# IE_ARSA_Merah_W_4_L.net
KiCad netlist of a schematic drawn in EAGLE
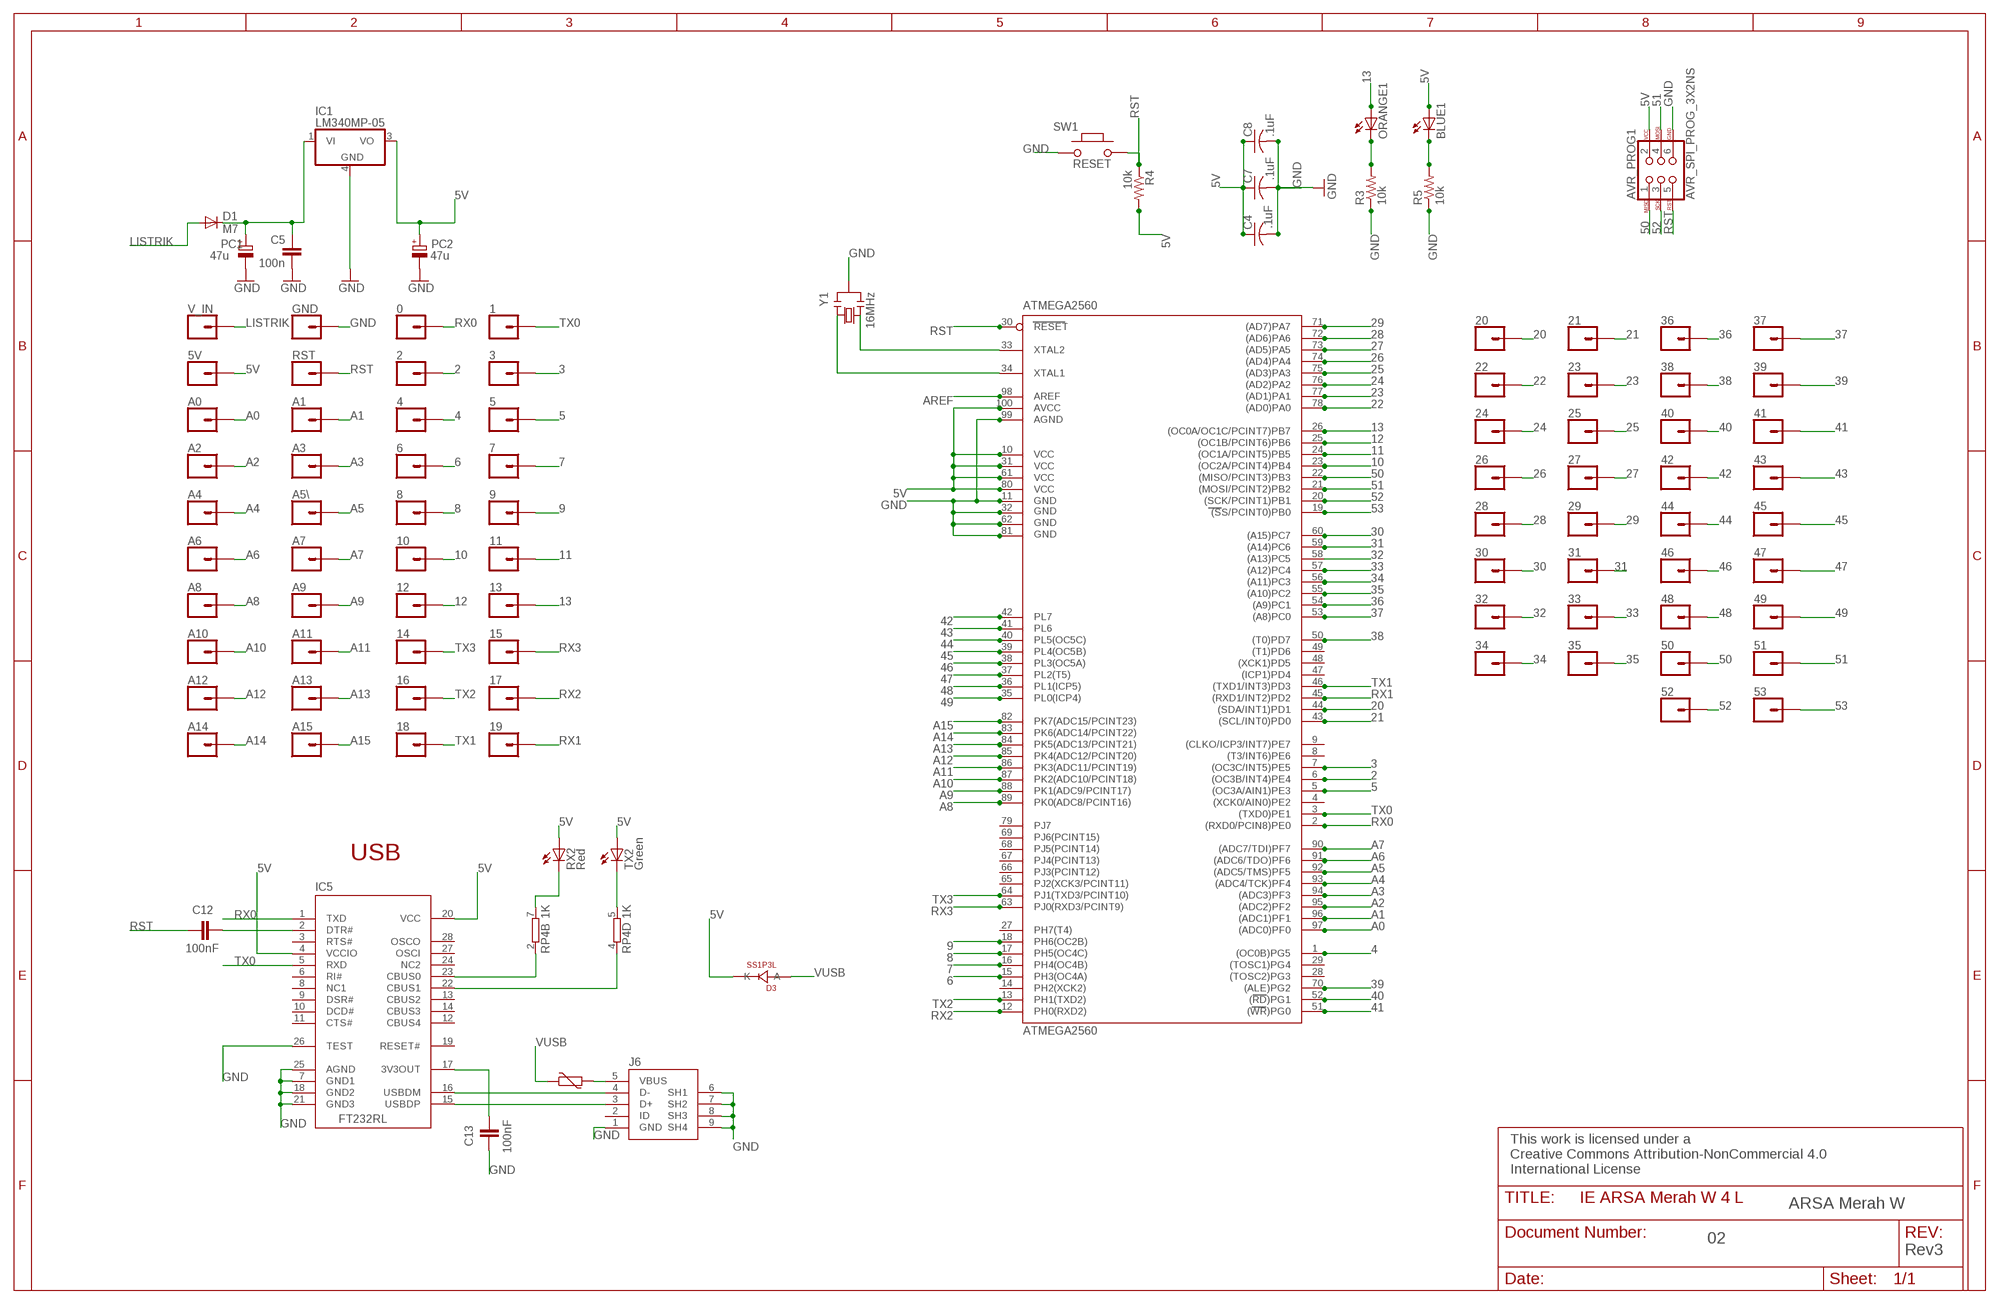
[diagram p0: schematic, sheet 1]

(export (version "E")
  (design (tool "Eeschema 10.0.6"))
  (components
    (comp (ref "0")
      (value "CONN_01")
      (footprint "eagle-import:1X01")
      (libsource (lib "eagle-import") (part "CONN_01"))
    )
    (comp (ref "1")
      (value "CONN_01")
      (footprint "eagle-import:1X01")
      (libsource (lib "eagle-import") (part "CONN_01"))
    )
    (comp (ref "2")
      (value "CONN_01")
      (footprint "eagle-import:1X01")
      (libsource (lib "eagle-import") (part "CONN_01"))
    )
    (comp (ref "3")
      (value "CONN_01")
      (footprint "eagle-import:1X01")
      (libsource (lib "eagle-import") (part "CONN_01"))
    )
    (comp (ref "4")
      (value "CONN_01")
      (footprint "eagle-import:1X01")
      (libsource (lib "eagle-import") (part "CONN_01"))
    )
    (comp (ref "5")
      (value "CONN_01")
      (footprint "eagle-import:1X01")
      (libsource (lib "eagle-import") (part "CONN_01"))
    )
    (comp (ref "5V")
      (value "CONN_01")
      (footprint "eagle-import:1X01")
      (libsource (lib "eagle-import") (part "CONN_01"))
    )
    (comp (ref "6")
      (value "CONN_01")
      (footprint "eagle-import:1X01")
      (libsource (lib "eagle-import") (part "CONN_01"))
    )
    (comp (ref "7")
      (value "CONN_01")
      (footprint "eagle-import:1X01")
      (libsource (lib "eagle-import") (part "CONN_01"))
    )
    (comp (ref "8")
      (value "CONN_01")
      (footprint "eagle-import:1X01")
      (libsource (lib "eagle-import") (part "CONN_01"))
    )
    (comp (ref "9")
      (value "CONN_01")
      (footprint "eagle-import:1X01")
      (libsource (lib "eagle-import") (part "CONN_01"))
    )
    (comp (ref "10")
      (value "CONN_01")
      (footprint "eagle-import:1X01")
      (libsource (lib "eagle-import") (part "CONN_01"))
    )
    (comp (ref "11")
      (value "CONN_01")
      (footprint "eagle-import:1X01")
      (libsource (lib "eagle-import") (part "CONN_01"))
    )
    (comp (ref "12")
      (value "CONN_01")
      (footprint "eagle-import:1X01")
      (libsource (lib "eagle-import") (part "CONN_01"))
    )
    (comp (ref "13")
      (value "CONN_01")
      (footprint "eagle-import:1X01")
      (libsource (lib "eagle-import") (part "CONN_01"))
    )
    (comp (ref "14")
      (value "CONN_01")
      (footprint "eagle-import:1X01")
      (libsource (lib "eagle-import") (part "CONN_01"))
    )
    (comp (ref "15")
      (value "CONN_01")
      (footprint "eagle-import:1X01")
      (libsource (lib "eagle-import") (part "CONN_01"))
    )
    (comp (ref "16")
      (value "CONN_01")
      (footprint "eagle-import:1X01")
      (libsource (lib "eagle-import") (part "CONN_01"))
    )
    (comp (ref "17")
      (value "CONN_01")
      (footprint "eagle-import:1X01")
      (libsource (lib "eagle-import") (part "CONN_01"))
    )
    (comp (ref "18")
      (value "CONN_01")
      (footprint "eagle-import:1X01")
      (libsource (lib "eagle-import") (part "CONN_01"))
    )
    (comp (ref "19")
      (value "CONN_01")
      (footprint "eagle-import:1X01")
      (libsource (lib "eagle-import") (part "CONN_01"))
    )
    (comp (ref "20")
      (value "CONN_01")
      (footprint "eagle-import:1X01")
      (libsource (lib "eagle-import") (part "CONN_01"))
    )
    (comp (ref "21")
      (value "CONN_01")
      (footprint "eagle-import:1X01")
      (libsource (lib "eagle-import") (part "CONN_01"))
    )
    (comp (ref "22")
      (value "CONN_01")
      (footprint "eagle-import:1X01")
      (libsource (lib "eagle-import") (part "CONN_01"))
    )
    (comp (ref "23")
      (value "CONN_01")
      (footprint "eagle-import:1X01")
      (libsource (lib "eagle-import") (part "CONN_01"))
    )
    (comp (ref "24")
      (value "CONN_01")
      (footprint "eagle-import:1X01")
      (libsource (lib "eagle-import") (part "CONN_01"))
    )
    (comp (ref "25")
      (value "CONN_01")
      (footprint "eagle-import:1X01")
      (libsource (lib "eagle-import") (part "CONN_01"))
    )
    (comp (ref "26")
      (value "CONN_01")
      (footprint "eagle-import:1X01")
      (libsource (lib "eagle-import") (part "CONN_01"))
    )
    (comp (ref "27")
      (value "CONN_01")
      (footprint "eagle-import:1X01")
      (libsource (lib "eagle-import") (part "CONN_01"))
    )
    (comp (ref "28")
      (value "CONN_01")
      (footprint "eagle-import:1X01")
      (libsource (lib "eagle-import") (part "CONN_01"))
    )
    (comp (ref "29")
      (value "CONN_01")
      (footprint "eagle-import:1X01")
      (libsource (lib "eagle-import") (part "CONN_01"))
    )
    (comp (ref "30")
      (value "CONN_01")
      (footprint "eagle-import:1X01")
      (libsource (lib "eagle-import") (part "CONN_01"))
    )
    (comp (ref "31")
      (value "CONN_01")
      (footprint "eagle-import:1X01")
      (libsource (lib "eagle-import") (part "CONN_01"))
    )
    (comp (ref "32")
      (value "CONN_01")
      (footprint "eagle-import:1X01")
      (libsource (lib "eagle-import") (part "CONN_01"))
    )
    (comp (ref "33")
      (value "CONN_01")
      (footprint "eagle-import:1X01")
      (libsource (lib "eagle-import") (part "CONN_01"))
    )
    (comp (ref "34")
      (value "CONN_01")
      (footprint "eagle-import:1X01")
      (libsource (lib "eagle-import") (part "CONN_01"))
    )
    (comp (ref "35")
      (value "CONN_01")
      (footprint "eagle-import:1X01")
      (libsource (lib "eagle-import") (part "CONN_01"))
    )
    (comp (ref "36")
      (value "CONN_01")
      (footprint "eagle-import:1X01")
      (libsource (lib "eagle-import") (part "CONN_01"))
    )
    (comp (ref "37")
      (value "CONN_01")
      (footprint "eagle-import:1X01")
      (libsource (lib "eagle-import") (part "CONN_01"))
    )
    (comp (ref "38")
      (value "CONN_01")
      (footprint "eagle-import:1X01")
      (libsource (lib "eagle-import") (part "CONN_01"))
    )
    (comp (ref "39")
      (value "CONN_01")
      (footprint "eagle-import:1X01")
      (libsource (lib "eagle-import") (part "CONN_01"))
    )
    (comp (ref "40")
      (value "CONN_01")
      (footprint "eagle-import:1X01")
      (libsource (lib "eagle-import") (part "CONN_01"))
    )
    (comp (ref "41")
      (value "CONN_01")
      (footprint "eagle-import:1X01")
      (libsource (lib "eagle-import") (part "CONN_01"))
    )
    (comp (ref "42")
      (value "CONN_01")
      (footprint "eagle-import:1X01")
      (libsource (lib "eagle-import") (part "CONN_01"))
    )
    (comp (ref "43")
      (value "CONN_01")
      (footprint "eagle-import:1X01")
      (libsource (lib "eagle-import") (part "CONN_01"))
    )
    (comp (ref "44")
      (value "CONN_01")
      (footprint "eagle-import:1X01")
      (libsource (lib "eagle-import") (part "CONN_01"))
    )
    (comp (ref "45")
      (value "CONN_01")
      (footprint "eagle-import:1X01")
      (libsource (lib "eagle-import") (part "CONN_01"))
    )
    (comp (ref "46")
      (value "CONN_01")
      (footprint "eagle-import:1X01")
      (libsource (lib "eagle-import") (part "CONN_01"))
    )
    (comp (ref "47")
      (value "CONN_01")
      (footprint "eagle-import:1X01")
      (libsource (lib "eagle-import") (part "CONN_01"))
    )
    (comp (ref "48")
      (value "CONN_01")
      (footprint "eagle-import:1X01")
      (libsource (lib "eagle-import") (part "CONN_01"))
    )
    (comp (ref "49")
      (value "CONN_01")
      (footprint "eagle-import:1X01")
      (libsource (lib "eagle-import") (part "CONN_01"))
    )
    (comp (ref "50")
      (value "CONN_01")
      (footprint "eagle-import:1X01")
      (libsource (lib "eagle-import") (part "CONN_01"))
    )
    (comp (ref "51")
      (value "CONN_01")
      (footprint "eagle-import:1X01")
      (libsource (lib "eagle-import") (part "CONN_01"))
    )
    (comp (ref "52")
      (value "CONN_01")
      (footprint "eagle-import:1X01")
      (libsource (lib "eagle-import") (part "CONN_01"))
    )
    (comp (ref "53")
      (value "CONN_01")
      (footprint "eagle-import:1X01")
      (libsource (lib "eagle-import") (part "CONN_01"))
    )
    (comp (ref "A0")
      (value "CONN_01")
      (footprint "eagle-import:1X01")
      (libsource (lib "eagle-import") (part "CONN_01"))
    )
    (comp (ref "A1")
      (value "CONN_01")
      (footprint "eagle-import:1X01")
      (libsource (lib "eagle-import") (part "CONN_01"))
    )
    (comp (ref "A2")
      (value "CONN_01")
      (footprint "eagle-import:1X01")
      (libsource (lib "eagle-import") (part "CONN_01"))
    )
    (comp (ref "A3")
      (value "CONN_01")
      (footprint "eagle-import:1X01")
      (libsource (lib "eagle-import") (part "CONN_01"))
    )
    (comp (ref "A4")
      (value "CONN_01")
      (footprint "eagle-import:1X01")
      (libsource (lib "eagle-import") (part "CONN_01"))
    )
    (comp (ref "A5\\")
      (value "CONN_01")
      (footprint "eagle-import:1X01")
      (libsource (lib "eagle-import") (part "CONN_01"))
    )
    (comp (ref "A6")
      (value "CONN_01")
      (footprint "eagle-import:1X01")
      (libsource (lib "eagle-import") (part "CONN_01"))
    )
    (comp (ref "A7")
      (value "CONN_01")
      (footprint "eagle-import:1X01")
      (libsource (lib "eagle-import") (part "CONN_01"))
    )
    (comp (ref "A8")
      (value "CONN_01")
      (footprint "eagle-import:1X01")
      (libsource (lib "eagle-import") (part "CONN_01"))
    )
    (comp (ref "A9")
      (value "CONN_01")
      (footprint "eagle-import:1X01")
      (libsource (lib "eagle-import") (part "CONN_01"))
    )
    (comp (ref "A10")
      (value "CONN_01")
      (footprint "eagle-import:1X01")
      (libsource (lib "eagle-import") (part "CONN_01"))
    )
    (comp (ref "A11")
      (value "CONN_01")
      (footprint "eagle-import:1X01")
      (libsource (lib "eagle-import") (part "CONN_01"))
    )
    (comp (ref "A12")
      (value "CONN_01")
      (footprint "eagle-import:1X01")
      (libsource (lib "eagle-import") (part "CONN_01"))
    )
    (comp (ref "A13")
      (value "CONN_01")
      (footprint "eagle-import:1X01")
      (libsource (lib "eagle-import") (part "CONN_01"))
    )
    (comp (ref "A14")
      (value "CONN_01")
      (footprint "eagle-import:1X01")
      (libsource (lib "eagle-import") (part "CONN_01"))
    )
    (comp (ref "A15")
      (value "CONN_01")
      (footprint "eagle-import:1X01")
      (libsource (lib "eagle-import") (part "CONN_01"))
    )
    (comp (ref "ATMEGA2560")
      (value "ATMEGA2560")
      (footprint "eagle-import:TQFP100")
      (libsource (lib "eagle-import") (part "ATMEGA2560"))
    )
    (comp (ref "AVR_PROG1")
      (value "AVR_SPI_PROG_3X2NS")
      (footprint "eagle-import:2X3-NS")
      (libsource (lib "eagle-import") (part "AVR_SPI_PROG_3X2NS"))
    )
    (comp (ref "BLUE1")
      (value "L")
      (footprint "eagle-import:SMD-0805-LED")
      (libsource (lib "eagle-import") (part "LED-SMD-0805"))
    )
    (comp (ref "C4")
      (value "CAPACITOR-SMD-0805")
      (footprint "eagle-import:SMD-0805")
      (libsource (lib "eagle-import") (part "CAPACITOR-SMD-0805"))
    )
    (comp (ref "C5")
      (value "100n")
      (footprint "eagle-import:C0603-ROUND")
      (libsource (lib "eagle-import") (part "C-EU0603-RND"))
    )
    (comp (ref "C7")
      (value ".1uF")
      (footprint "eagle-import:SMD-0805")
      (libsource (lib "eagle-import") (part "CAPACITOR-SMD-0805"))
    )
    (comp (ref "C8")
      (value ".1uF")
      (footprint "eagle-import:SMD-0805")
      (libsource (lib "eagle-import") (part "CAPACITOR-SMD-0805"))
    )
    (comp (ref "C12")
      (value "100nF")
      (footprint "eagle-import:C0603-ROUND")
      (fields (field (name "PART_NUMBER") "cl10b104kbnc"))
      (libsource (lib "eagle-import") (part "0015_100NF_0603"))
    )
    (comp (ref "C13")
      (value "100nF")
      (footprint "eagle-import:C0603-ROUND")
      (fields (field (name "PART_NUMBER") "cl10b104kbnc"))
      (libsource (lib "eagle-import") (part "0015_100NF_0603"))
    )
    (comp (ref "D1")
      (value "M7")
      (footprint "eagle-import:SMB")
      (libsource (lib "eagle-import") (part "DIODE-SMB"))
    )
    (comp (ref "D3")
      (value "SS1P3L")
      (footprint "eagle-import:DO220AAL")
      (fields (field (name "PART_NUMBER") "SS1P3L-M3/84A"))
      (libsource (lib "eagle-import") (part "0025_SS1P3L-M3/84A"))
    )
    (comp (ref "F3")
      (value "MFFSMF050")
      (footprint "eagle-import:0603-1608X90N")
      (fields (field (name "MANUFACTURER") "Bourns Inc "))
      (libsource (lib "eagle-import") (part "PTC"))
    )
    (comp (ref "GND")
      (value "CONN_01")
      (footprint "eagle-import:1X01")
      (libsource (lib "eagle-import") (part "CONN_01"))
    )
    (comp (ref "IC1")
      (value "LM340MP-05")
      (footprint "eagle-import:SOT223")
      (libsource (lib "eagle-import") (part "LM340?-MP05"))
    )
    (comp (ref "IC5")
      (value "FT232RL")
      (footprint "eagle-import:SSOP28")
      (libsource (lib "eagle-import") (part "0226_FT232RL"))
    )
    (comp (ref "J6")
      (value "0219_14850")
      (footprint "eagle-import:USB-MINI-B_2")
      (fields (field (name "PART_NUMBER") "14850"))
      (libsource (lib "eagle-import") (part "0219_14850"))
    )
    (comp (ref "ORANGE1")
      (value "L")
      (footprint "eagle-import:SMD-0805-LED")
      (libsource (lib "eagle-import") (part "LED-SMD-0805"))
    )
    (comp (ref "PC1")
      (value "47u")
      (footprint "eagle-import:PANASONIC_D")
      (libsource (lib "eagle-import") (part "CPOL-EUD"))
    )
    (comp (ref "PC2")
      (value "47u")
      (footprint "eagle-import:PANASONIC_D")
      (libsource (lib "eagle-import") (part "CPOL-EUD"))
    )
    (comp (ref "R3")
      (value "10k")
      (footprint "eagle-import:SMD-0805")
      (libsource (lib "eagle-import") (part "RESISTOR-SMD-0805"))
    )
    (comp (ref "R4")
      (value "10k")
      (footprint "eagle-import:SMD-0805")
      (libsource (lib "eagle-import") (part "RESISTOR-SMD-0805"))
    )
    (comp (ref "R5")
      (value "10k")
      (footprint "eagle-import:SMD-0805")
      (libsource (lib "eagle-import") (part "RESISTOR-SMD-0805"))
    )
    (comp (ref "RP4")
      (value "1K")
      (footprint "eagle-import:CAY16")
      (fields (field (name "PART_NUMBER") "064R_1K_/_CAY16-102J4LF"))
      (libsource (lib "eagle-import") (part "0005_064R_1K_/_CAY16-102J4LF"))
    )
    (comp (ref "RST")
      (value "CONN_01")
      (footprint "eagle-import:1X01")
      (libsource (lib "eagle-import") (part "CONN_01"))
    )
    (comp (ref "RX2")
      (value "Red")
      (footprint "eagle-import:CHIPLED_0805")
      (fields (field (name "PART_NUMBER") "KTP-2012SURCK"))
      (libsource (lib "eagle-import") (part "0181_KTP-2012SURCK"))
    )
    (comp (ref "SW1")
      (value "RESET")
      (footprint "eagle-import:SMD_157SW")
      (fields (field (name "PART_NUMBER") "IT-1185AP1C-160G-G_T&R"))
      (libsource (lib "eagle-import") (part "0173_IT-1185AP1C-160G-G_T&R"))
    )
    (comp (ref "TX2")
      (value "Green")
      (footprint "eagle-import:CHIPLED_0805")
      (fields (field (name "PART_NUMBER") "KPT-2012SGC"))
      (libsource (lib "eagle-import") (part "0043_KPT-2012SGC"))
    )
    (comp (ref "V_IN")
      (value "CONN_01")
      (footprint "eagle-import:1X01")
      (libsource (lib "eagle-import") (part "CONN_01"))
    )
    (comp (ref "Y1")
      (value "16MHz")
      (footprint "eagle-import:RESONATOR")
      (fields (field (name "PART_NUMBER") "CSTCE16M0V53-R0"))
      (libsource (lib "eagle-import") (part "0011_CSTCE16M0V53-R0"))
    )
  )
  (nets
    (net (code "1") (name "/LISTRIK") (class "Default")
      (node (ref "D1") (pin "A") (pinfunction "A_A") (pintype "passive"))
      (node (ref "V_IN") (pin "1") (pinfunction "1_1") (pintype "passive"))
    )
    (net (code "2") (name "/VUSB") (class "Default")
      (node (ref "D3") (pin "P$2") (pinfunction "A_P$2") (pintype "bidirectional"))
      (node (ref "F3") (pin "1") (pinfunction "1_1") (pintype "passive"))
    )
    (net (code "3") (name "2") (class "Default")
      (node (ref "2") (pin "1") (pinfunction "1_1") (pintype "passive"))
      (node (ref "ATMEGA2560") (pin "6") (pinfunction "(OC3B/INT4)PE4_6") (pintype "bidirectional"))
    )
    (net (code "4") (name "3") (class "Default")
      (node (ref "3") (pin "1") (pinfunction "1_1") (pintype "passive"))
      (node (ref "ATMEGA2560") (pin "7") (pinfunction "(OC3C/INT5)PE5_7") (pintype "bidirectional"))
    )
    (net (code "5") (name "4") (class "Default")
      (node (ref "4") (pin "1") (pinfunction "1_1") (pintype "passive"))
      (node (ref "ATMEGA2560") (pin "1") (pinfunction "(OC0B)PG5_1") (pintype "bidirectional"))
    )
    (net (code "6") (name "5") (class "Default")
      (node (ref "5") (pin "1") (pinfunction "1_1") (pintype "passive"))
      (node (ref "ATMEGA2560") (pin "5") (pinfunction "(OC3A/AIN1)PE3_5") (pintype "bidirectional"))
    )
    (net (code "7") (name "5V") (class "Default")
      (node (ref "5V") (pin "1") (pinfunction "1_1") (pintype "passive"))
      (node (ref "ATMEGA2560") (pin "10") (pinfunction "VCC_10") (pintype "power_in"))
      (node (ref "ATMEGA2560") (pin "100") (pinfunction "AVCC_100") (pintype "power_in"))
      (node (ref "ATMEGA2560") (pin "31") (pinfunction "VCC1_31") (pintype "power_in"))
      (node (ref "ATMEGA2560") (pin "61") (pinfunction "VCC2_61") (pintype "power_in"))
      (node (ref "ATMEGA2560") (pin "80") (pinfunction "VCC3_80") (pintype "power_in"))
      (node (ref "AVR_PROG1") (pin "2") (pinfunction "2_2") (pintype "passive"))
      (node (ref "BLUE1") (pin "1") (pinfunction "A_1") (pintype "passive"))
      (node (ref "C4") (pin "1") (pinfunction "1_1") (pintype "passive"))
      (node (ref "C7") (pin "1") (pinfunction "1_1") (pintype "passive"))
      (node (ref "C8") (pin "1") (pinfunction "1_1") (pintype "passive"))
      (node (ref "D3") (pin "P$1") (pinfunction "K_P$1") (pintype "bidirectional"))
      (node (ref "IC1") (pin "3") (pinfunction "VO_3") (pintype "passive"))
      (node (ref "IC5") (pin "20") (pinfunction "VCC_20") (pintype "power_in"))
      (node (ref "IC5") (pin "4") (pinfunction "VCCIO_4") (pintype "power_in"))
      (node (ref "PC2") (pin "+") (pinfunction "+_+") (pintype "passive"))
      (node (ref "R4") (pin "2") (pinfunction "2_2") (pintype "passive"))
      (node (ref "RX2") (pin "A") (pinfunction "A_A") (pintype "passive"))
      (node (ref "TX2") (pin "A") (pinfunction "A_A") (pintype "passive"))
    )
    (net (code "8") (name "6") (class "Default")
      (node (ref "6") (pin "1") (pinfunction "1_1") (pintype "passive"))
      (node (ref "ATMEGA2560") (pin "15") (pinfunction "PH3(OC4A)_15") (pintype "bidirectional"))
    )
    (net (code "9") (name "7") (class "Default")
      (node (ref "7") (pin "1") (pinfunction "1_1") (pintype "passive"))
      (node (ref "ATMEGA2560") (pin "16") (pinfunction "PH4(OC4B)_16") (pintype "bidirectional"))
    )
    (net (code "10") (name "8") (class "Default")
      (node (ref "8") (pin "1") (pinfunction "1_1") (pintype "passive"))
      (node (ref "ATMEGA2560") (pin "17") (pinfunction "PH5(OC4C)_17") (pintype "bidirectional"))
    )
    (net (code "11") (name "9") (class "Default")
      (node (ref "9") (pin "1") (pinfunction "1_1") (pintype "passive"))
      (node (ref "ATMEGA2560") (pin "18") (pinfunction "PH6(OC2B)_18") (pintype "bidirectional"))
    )
    (net (code "12") (name "10") (class "Default")
      (node (ref "10") (pin "1") (pinfunction "1_1") (pintype "passive"))
      (node (ref "ATMEGA2560") (pin "23") (pinfunction "(OC2A/PCINT4)PB4_23") (pintype "bidirectional"))
    )
    (net (code "13") (name "11") (class "Default")
      (node (ref "11") (pin "1") (pinfunction "1_1") (pintype "passive"))
      (node (ref "ATMEGA2560") (pin "24") (pinfunction "(OC1A/PCINT5)PB5_24") (pintype "bidirectional"))
    )
    (net (code "14") (name "12") (class "Default")
      (node (ref "12") (pin "1") (pinfunction "1_1") (pintype "passive"))
      (node (ref "ATMEGA2560") (pin "25") (pinfunction "(OC1B/PCINT6)PB6_25") (pintype "bidirectional"))
    )
    (net (code "15") (name "13") (class "Default")
      (node (ref "13") (pin "1") (pinfunction "1_1") (pintype "passive"))
      (node (ref "ATMEGA2560") (pin "26") (pinfunction "(OC0A/OC1C/PCINT7)PB7_26") (pintype "bidirectional"))
      (node (ref "ORANGE1") (pin "1") (pinfunction "A_1") (pintype "passive"))
    )
    (net (code "16") (name "20") (class "Default")
      (node (ref "20") (pin "1") (pinfunction "1_1") (pintype "passive"))
      (node (ref "ATMEGA2560") (pin "44") (pinfunction "(SDA/INT1)PD1_44") (pintype "bidirectional"))
    )
    (net (code "17") (name "21") (class "Default")
      (node (ref "21") (pin "1") (pinfunction "1_1") (pintype "passive"))
      (node (ref "ATMEGA2560") (pin "43") (pinfunction "(SCL/INT0)PD0_43") (pintype "bidirectional"))
    )
    (net (code "18") (name "22") (class "Default")
      (node (ref "22") (pin "1") (pinfunction "1_1") (pintype "passive"))
      (node (ref "ATMEGA2560") (pin "78") (pinfunction "(AD0)PA0_78") (pintype "bidirectional"))
    )
    (net (code "19") (name "23") (class "Default")
      (node (ref "23") (pin "1") (pinfunction "1_1") (pintype "passive"))
      (node (ref "ATMEGA2560") (pin "77") (pinfunction "(AD1)PA1_77") (pintype "bidirectional"))
    )
    (net (code "20") (name "24") (class "Default")
      (node (ref "24") (pin "1") (pinfunction "1_1") (pintype "passive"))
      (node (ref "ATMEGA2560") (pin "76") (pinfunction "(AD2)PA2_76") (pintype "bidirectional"))
    )
    (net (code "21") (name "25") (class "Default")
      (node (ref "25") (pin "1") (pinfunction "1_1") (pintype "passive"))
      (node (ref "ATMEGA2560") (pin "75") (pinfunction "(AD3)PA3_75") (pintype "bidirectional"))
    )
    (net (code "22") (name "26") (class "Default")
      (node (ref "26") (pin "1") (pinfunction "1_1") (pintype "passive"))
      (node (ref "ATMEGA2560") (pin "74") (pinfunction "(AD4)PA4_74") (pintype "bidirectional"))
    )
    (net (code "23") (name "27") (class "Default")
      (node (ref "27") (pin "1") (pinfunction "1_1") (pintype "passive"))
      (node (ref "ATMEGA2560") (pin "73") (pinfunction "(AD5)PA5_73") (pintype "bidirectional"))
    )
    (net (code "24") (name "28") (class "Default")
      (node (ref "28") (pin "1") (pinfunction "1_1") (pintype "passive"))
      (node (ref "ATMEGA2560") (pin "72") (pinfunction "(AD6)PA6_72") (pintype "bidirectional"))
    )
    (net (code "25") (name "29") (class "Default")
      (node (ref "29") (pin "1") (pinfunction "1_1") (pintype "passive"))
      (node (ref "ATMEGA2560") (pin "71") (pinfunction "(AD7)PA7_71") (pintype "bidirectional"))
    )
    (net (code "26") (name "30") (class "Default")
      (node (ref "30") (pin "1") (pinfunction "1_1") (pintype "passive"))
      (node (ref "ATMEGA2560") (pin "60") (pinfunction "(A15)PC7_60") (pintype "bidirectional"))
    )
    (net (code "27") (name "31") (class "Default")
      (node (ref "31") (pin "1") (pinfunction "1_1") (pintype "passive"))
      (node (ref "ATMEGA2560") (pin "59") (pinfunction "(A14)PC6_59") (pintype "bidirectional"))
    )
    (net (code "28") (name "32") (class "Default")
      (node (ref "32") (pin "1") (pinfunction "1_1") (pintype "passive"))
      (node (ref "ATMEGA2560") (pin "58") (pinfunction "(A13)PC5_58") (pintype "bidirectional"))
    )
    (net (code "29") (name "33") (class "Default")
      (node (ref "33") (pin "1") (pinfunction "1_1") (pintype "passive"))
      (node (ref "ATMEGA2560") (pin "57") (pinfunction "(A12)PC4_57") (pintype "bidirectional"))
    )
    (net (code "30") (name "34") (class "Default")
      (node (ref "34") (pin "1") (pinfunction "1_1") (pintype "passive"))
      (node (ref "ATMEGA2560") (pin "56") (pinfunction "(A11)PC3_56") (pintype "bidirectional"))
    )
    (net (code "31") (name "35") (class "Default")
      (node (ref "35") (pin "1") (pinfunction "1_1") (pintype "passive"))
      (node (ref "ATMEGA2560") (pin "55") (pinfunction "(A10)PC2_55") (pintype "bidirectional"))
    )
    (net (code "32") (name "36") (class "Default")
      (node (ref "36") (pin "1") (pinfunction "1_1") (pintype "passive"))
      (node (ref "ATMEGA2560") (pin "54") (pinfunction "(A9)PC1_54") (pintype "bidirectional"))
    )
    (net (code "33") (name "37") (class "Default")
      (node (ref "37") (pin "1") (pinfunction "1_1") (pintype "passive"))
      (node (ref "ATMEGA2560") (pin "53") (pinfunction "(A8)PC0_53") (pintype "bidirectional"))
    )
    (net (code "34") (name "38") (class "Default")
      (node (ref "38") (pin "1") (pinfunction "1_1") (pintype "passive"))
      (node (ref "ATMEGA2560") (pin "50") (pinfunction "(T0)PD7_50") (pintype "bidirectional"))
    )
    (net (code "35") (name "39") (class "Default")
      (node (ref "39") (pin "1") (pinfunction "1_1") (pintype "passive"))
      (node (ref "ATMEGA2560") (pin "70") (pinfunction "(ALE)PG2_70") (pintype "bidirectional"))
    )
    (net (code "36") (name "40") (class "Default")
      (node (ref "40") (pin "1") (pinfunction "1_1") (pintype "passive"))
      (node (ref "ATMEGA2560") (pin "52") (pinfunction "(RD)PG1_52") (pintype "bidirectional"))
    )
    (net (code "37") (name "41") (class "Default")
      (node (ref "41") (pin "1") (pinfunction "1_1") (pintype "passive"))
      (node (ref "ATMEGA2560") (pin "51") (pinfunction "(WR)PG0_51") (pintype "bidirectional"))
    )
    (net (code "38") (name "42") (class "Default")
      (node (ref "42") (pin "1") (pinfunction "1_1") (pintype "passive"))
      (node (ref "ATMEGA2560") (pin "42") (pinfunction "PL7_42") (pintype "bidirectional"))
    )
    (net (code "39") (name "43") (class "Default")
      (node (ref "43") (pin "1") (pinfunction "1_1") (pintype "passive"))
      (node (ref "ATMEGA2560") (pin "41") (pinfunction "PL6_41") (pintype "bidirectional"))
    )
    (net (code "40") (name "44") (class "Default")
      (node (ref "44") (pin "1") (pinfunction "1_1") (pintype "passive"))
      (node (ref "ATMEGA2560") (pin "40") (pinfunction "PL5(OC5C)_40") (pintype "bidirectional"))
    )
    (net (code "41") (name "45") (class "Default")
      (node (ref "45") (pin "1") (pinfunction "1_1") (pintype "passive"))
      (node (ref "ATMEGA2560") (pin "39") (pinfunction "PL4(OC5B)_39") (pintype "bidirectional"))
    )
    (net (code "42") (name "46") (class "Default")
      (node (ref "46") (pin "1") (pinfunction "1_1") (pintype "passive"))
      (node (ref "ATMEGA2560") (pin "38") (pinfunction "PL3(OC5A)_38") (pintype "bidirectional"))
    )
    (net (code "43") (name "47") (class "Default")
      (node (ref "47") (pin "1") (pinfunction "1_1") (pintype "passive"))
      (node (ref "ATMEGA2560") (pin "37") (pinfunction "PL2(T5)_37") (pintype "bidirectional"))
    )
    (net (code "44") (name "48") (class "Default")
      (node (ref "48") (pin "1") (pinfunction "1_1") (pintype "passive"))
      (node (ref "ATMEGA2560") (pin "36") (pinfunction "PL1(ICP5)_36") (pintype "bidirectional"))
    )
    (net (code "45") (name "49") (class "Default")
      (node (ref "49") (pin "1") (pinfunction "1_1") (pintype "passive"))
      (node (ref "ATMEGA2560") (pin "35") (pinfunction "PL0(ICP4)_35") (pintype "bidirectional"))
    )
    (net (code "46") (name "50") (class "Default")
      (node (ref "50") (pin "1") (pinfunction "1_1") (pintype "passive"))
      (node (ref "ATMEGA2560") (pin "22") (pinfunction "(MISO/PCINT3)PB3_22") (pintype "bidirectional"))
      (node (ref "AVR_PROG1") (pin "1") (pinfunction "1_1") (pintype "passive"))
    )
    (net (code "47") (name "51") (class "Default")
      (node (ref "51") (pin "1") (pinfunction "1_1") (pintype "passive"))
      (node (ref "ATMEGA2560") (pin "21") (pinfunction "(MOSI/PCINT2)PB2_21") (pintype "bidirectional"))
      (node (ref "AVR_PROG1") (pin "4") (pinfunction "4_4") (pintype "passive"))
    )
    (net (code "48") (name "52") (class "Default")
      (node (ref "52") (pin "1") (pinfunction "1_1") (pintype "passive"))
      (node (ref "ATMEGA2560") (pin "20") (pinfunction "(SCK/PCINT1)PB1_20") (pintype "bidirectional"))
      (node (ref "AVR_PROG1") (pin "3") (pinfunction "3_3") (pintype "passive"))
    )
    (net (code "49") (name "53") (class "Default")
      (node (ref "53") (pin "1") (pinfunction "1_1") (pintype "passive"))
      (node (ref "ATMEGA2560") (pin "19") (pinfunction "(SS/PCINT0)PB0_19") (pintype "bidirectional"))
    )
    (net (code "50") (name "A0") (class "Default")
      (node (ref "A0") (pin "1") (pinfunction "1_1") (pintype "passive"))
      (node (ref "ATMEGA2560") (pin "97") (pinfunction "(ADC0)PF0_97") (pintype "bidirectional"))
    )
    (net (code "51") (name "A1") (class "Default")
      (node (ref "A1") (pin "1") (pinfunction "1_1") (pintype "passive"))
      (node (ref "ATMEGA2560") (pin "96") (pinfunction "(ADC1)PF1_96") (pintype "bidirectional"))
    )
    (net (code "52") (name "A2") (class "Default")
      (node (ref "A2") (pin "1") (pinfunction "1_1") (pintype "passive"))
      (node (ref "ATMEGA2560") (pin "95") (pinfunction "(ADC2)PF2_95") (pintype "bidirectional"))
    )
    (net (code "53") (name "A3") (class "Default")
      (node (ref "A3") (pin "1") (pinfunction "1_1") (pintype "passive"))
      (node (ref "ATMEGA2560") (pin "94") (pinfunction "(ADC3)PF3_94") (pintype "bidirectional"))
    )
    (net (code "54") (name "A4") (class "Default")
      (node (ref "A4") (pin "1") (pinfunction "1_1") (pintype "passive"))
      (node (ref "ATMEGA2560") (pin "93") (pinfunction "(ADC4/TCK)PF4_93") (pintype "bidirectional"))
    )
    (net (code "55") (name "A5") (class "Default")
      (node (ref "A5\\") (pin "1") (pinfunction "1_1") (pintype "passive"))
      (node (ref "ATMEGA2560") (pin "92") (pinfunction "(ADC5/TMS)PF5_92") (pintype "bidirectional"))
    )
    (net (code "56") (name "A6") (class "Default")
      (node (ref "A6") (pin "1") (pinfunction "1_1") (pintype "passive"))
      (node (ref "ATMEGA2560") (pin "91") (pinfunction "(ADC6/TDO)PF6_91") (pintype "bidirectional"))
    )
    (net (code "57") (name "A7") (class "Default")
      (node (ref "A7") (pin "1") (pinfunction "1_1") (pintype "passive"))
      (node (ref "ATMEGA2560") (pin "90") (pinfunction "(ADC7/TDI)PF7_90") (pintype "bidirectional"))
    )
    (net (code "58") (name "A8") (class "Default")
      (node (ref "A8") (pin "1") (pinfunction "1_1") (pintype "passive"))
      (node (ref "ATMEGA2560") (pin "89") (pinfunction "PK0(ADC8/PCINT16)_89") (pintype "bidirectional"))
    )
    (net (code "59") (name "A9") (class "Default")
      (node (ref "A9") (pin "1") (pinfunction "1_1") (pintype "passive"))
      (node (ref "ATMEGA2560") (pin "88") (pinfunction "PK1(ADC9/PCINT17)_88") (pintype "bidirectional"))
    )
    (net (code "60") (name "A10") (class "Default")
      (node (ref "A10") (pin "1") (pinfunction "1_1") (pintype "passive"))
      (node (ref "ATMEGA2560") (pin "87") (pinfunction "PK2(ADC10/PCINT18)_87") (pintype "bidirectional"))
    )
    (net (code "61") (name "A11") (class "Default")
      (node (ref "A11") (pin "1") (pinfunction "1_1") (pintype "passive"))
      (node (ref "ATMEGA2560") (pin "86") (pinfunction "PK3(ADC11/PCINT19)_86") (pintype "bidirectional"))
    )
    (net (code "62") (name "A12") (class "Default")
      (node (ref "A12") (pin "1") (pinfunction "1_1") (pintype "passive"))
      (node (ref "ATMEGA2560") (pin "85") (pinfunction "PK4(ADC12/PCINT20)_85") (pintype "bidirectional"))
    )
    (net (code "63") (name "A13") (class "Default")
      (node (ref "A13") (pin "1") (pinfunction "1_1") (pintype "passive"))
      (node (ref "ATMEGA2560") (pin "84") (pinfunction "PK5(ADC13/PCINT21)_84") (pintype "bidirectional"))
    )
    (net (code "64") (name "A14") (class "Default")
      (node (ref "A14") (pin "1") (pinfunction "1_1") (pintype "passive"))
      (node (ref "ATMEGA2560") (pin "83") (pinfunction "PK6(ADC14/PCINT22)_83") (pintype "bidirectional"))
    )
    (net (code "65") (name "A15") (class "Default")
      (node (ref "A15") (pin "1") (pinfunction "1_1") (pintype "passive"))
      (node (ref "ATMEGA2560") (pin "82") (pinfunction "PK7(ADC15/PCINT23)_82") (pintype "bidirectional"))
    )
    (net (code "66") (name "AREF") (class "Default")
      (node (ref "ATMEGA2560") (pin "98") (pinfunction "AREF_98") (pintype "bidirectional"))
    )
    (net (code "67") (name "GND") (class "Default")
      (node (ref "ATMEGA2560") (pin "11") (pinfunction "GND_11") (pintype "power_in"))
      (node (ref "ATMEGA2560") (pin "32") (pinfunction "GND1_32") (pintype "power_in"))
      (node (ref "ATMEGA2560") (pin "62") (pinfunction "GND2_62") (pintype "power_in"))
      (node (ref "ATMEGA2560") (pin "81") (pinfunction "GND3_81") (pintype "power_in"))
      (node (ref "ATMEGA2560") (pin "99") (pinfunction "AGND_99") (pintype "power_in"))
      (node (ref "AVR_PROG1") (pin "6") (pinfunction "6_6") (pintype "passive"))
      (node (ref "C13") (pin "1") (pinfunction "1_1") (pintype "passive"))
      (node (ref "C4") (pin "2") (pinfunction "2_2") (pintype "passive"))
      (node (ref "C5") (pin "2") (pinfunction "2_2") (pintype "passive"))
      (node (ref "C7") (pin "2") (pinfunction "2_2") (pintype "passive"))
      (node (ref "C8") (pin "2") (pinfunction "2_2") (pintype "passive"))
      (node (ref "GND") (pin "1") (pinfunction "1_1") (pintype "passive"))
      (node (ref "IC1") (pin "4") (pinfunction "GND_4") (pintype "passive"))
      (node (ref "IC5") (pin "18") (pinfunction "GND2_18") (pintype "power_in"))
      (node (ref "IC5") (pin "21") (pinfunction "GND3_21") (pintype "power_in"))
      (node (ref "IC5") (pin "25") (pinfunction "AGND_25") (pintype "power_in"))
      (node (ref "IC5") (pin "26") (pinfunction "TEST_26") (pintype "bidirectional"))
      (node (ref "IC5") (pin "7") (pinfunction "GND1_7") (pintype "power_in"))
      (node (ref "J6") (pin "1") (pinfunction "GND_1") (pintype "passive"))
      (node (ref "J6") (pin "6") (pinfunction "SH1_6") (pintype "passive"))
      (node (ref "J6") (pin "7") (pinfunction "SH2_7") (pintype "passive"))
      (node (ref "J6") (pin "8") (pinfunction "SH3_8") (pintype "passive"))
      (node (ref "J6") (pin "9") (pinfunction "SH4_9") (pintype "passive"))
      (node (ref "PC1") (pin "-") (pinfunction "-_-") (pintype "passive"))
      (node (ref "PC2") (pin "-") (pinfunction "-_-") (pintype "passive"))
      (node (ref "R3") (pin "1") (pinfunction "1_1") (pintype "passive"))
      (node (ref "R5") (pin "1") (pinfunction "1_1") (pintype "passive"))
      (node (ref "SW1") (pin "1") (pinfunction "1_1") (pintype "passive"))
      (node (ref "Y1") (pin "2") (pinfunction "2_2") (pintype "passive"))
    )
    (net (code "68") (name "Net-(ATMEGA2560-XTAL1)") (class "Default")
      (node (ref "ATMEGA2560") (pin "34") (pinfunction "XTAL1_34") (pintype "input"))
      (node (ref "Y1") (pin "1") (pinfunction "1_1") (pintype "passive"))
    )
    (net (code "69") (name "Net-(ATMEGA2560-XTAL2)") (class "Default")
      (node (ref "ATMEGA2560") (pin "33") (pinfunction "XTAL2_33") (pintype "output"))
      (node (ref "Y1") (pin "3") (pinfunction "3_3") (pintype "passive"))
    )
    (net (code "70") (name "Net-(BLUE1-C)") (class "Default")
      (node (ref "BLUE1") (pin "2") (pinfunction "C_2") (pintype "passive"))
      (node (ref "R5") (pin "2") (pinfunction "2_2") (pintype "passive"))
    )
    (net (code "71") (name "Net-(IC1-VI)") (class "Default")
      (node (ref "C5") (pin "1") (pinfunction "1_1") (pintype "passive"))
      (node (ref "D1") (pin "C") (pinfunction "C_C") (pintype "passive"))
      (node (ref "IC1") (pin "1") (pinfunction "VI_1") (pintype "input"))
      (node (ref "PC1") (pin "+") (pinfunction "+_+") (pintype "passive"))
    )
    (net (code "72") (name "Net-(IC5-3V3OUT)") (class "Default")
      (node (ref "C13") (pin "2") (pinfunction "2_2") (pintype "passive"))
      (node (ref "IC5") (pin "17") (pinfunction "3V3OUT_17") (pintype "power_in"))
    )
    (net (code "73") (name "Net-(IC5-CBUS0)") (class "Default")
      (node (ref "IC5") (pin "23") (pinfunction "CBUS0_23") (pintype "bidirectional"))
      (node (ref "RP4") (pin "2") (pinfunction "1_2") (pintype "passive"))
    )
    (net (code "74") (name "Net-(IC5-CBUS1)") (class "Default")
      (node (ref "IC5") (pin "22") (pinfunction "CBUS1_22") (pintype "bidirectional"))
      (node (ref "RP4") (pin "4") (pinfunction "1_4") (pintype "passive"))
    )
    (net (code "75") (name "Net-(IC5-DTR#)") (class "Default")
      (node (ref "C12") (pin "2") (pinfunction "2_2") (pintype "passive"))
      (node (ref "IC5") (pin "2") (pinfunction "DTR#_2") (pintype "output"))
    )
    (net (code "76") (name "Net-(IC5-USBDM)") (class "Default")
      (node (ref "IC5") (pin "16") (pinfunction "USBDM_16") (pintype "bidirectional"))
      (node (ref "J6") (pin "4") (pinfunction "D-_4") (pintype "bidirectional"))
    )
    (net (code "77") (name "Net-(IC5-USBDP)") (class "Default")
      (node (ref "IC5") (pin "15") (pinfunction "USBDP_15") (pintype "bidirectional"))
      (node (ref "J6") (pin "3") (pinfunction "D+_3") (pintype "bidirectional"))
    )
    (net (code "78") (name "Net-(J6-VBUS)") (class "Default")
      (node (ref "F3") (pin "2") (pinfunction "2_2") (pintype "passive"))
      (node (ref "J6") (pin "5") (pinfunction "VBUS_5") (pintype "power_in"))
    )
    (net (code "79") (name "Net-(ORANGE1-C)") (class "Default")
      (node (ref "ORANGE1") (pin "2") (pinfunction "C_2") (pintype "passive"))
      (node (ref "R3") (pin "2") (pinfunction "2_2") (pintype "passive"))
    )
    (net (code "80") (name "Net-(RP4B-2)") (class "Default")
      (node (ref "RP4") (pin "7") (pinfunction "2_7") (pintype "passive"))
      (node (ref "RX2") (pin "C") (pinfunction "C_C") (pintype "passive"))
    )
    (net (code "81") (name "Net-(RP4D-2)") (class "Default")
      (node (ref "RP4") (pin "5") (pinfunction "2_5") (pintype "passive"))
      (node (ref "TX2") (pin "C") (pinfunction "C_C") (pintype "passive"))
    )
    (net (code "82") (name "RST") (class "Default")
      (node (ref "ATMEGA2560") (pin "30") (pinfunction "RESET_30") (pintype "input"))
      (node (ref "AVR_PROG1") (pin "5") (pinfunction "5_5") (pintype "passive"))
      (node (ref "C12") (pin "1") (pinfunction "1_1") (pintype "passive"))
      (node (ref "R4") (pin "1") (pinfunction "1_1") (pintype "passive"))
      (node (ref "RST") (pin "1") (pinfunction "1_1") (pintype "passive"))
      (node (ref "SW1") (pin "2") (pinfunction "2_2") (pintype "passive"))
    )
    (net (code "83") (name "RX0") (class "Default")
      (node (ref "0") (pin "1") (pinfunction "1_1") (pintype "passive"))
      (node (ref "ATMEGA2560") (pin "2") (pinfunction "(RXD0/PCIN8)PE0_2") (pintype "bidirectional"))
      (node (ref "IC5") (pin "1") (pinfunction "TXD_1") (pintype "output"))
    )
    (net (code "84") (name "RX1") (class "Default")
      (node (ref "19") (pin "1") (pinfunction "1_1") (pintype "passive"))
      (node (ref "ATMEGA2560") (pin "45") (pinfunction "(RXD1/INT2)PD2_45") (pintype "bidirectional"))
    )
    (net (code "85") (name "RX2") (class "Default")
      (node (ref "17") (pin "1") (pinfunction "1_1") (pintype "passive"))
      (node (ref "ATMEGA2560") (pin "12") (pinfunction "PH0(RXD2)_12") (pintype "bidirectional"))
    )
    (net (code "86") (name "RX3") (class "Default")
      (node (ref "15") (pin "1") (pinfunction "1_1") (pintype "passive"))
      (node (ref "ATMEGA2560") (pin "63") (pinfunction "PJ0(RXD3/PCINT9)_63") (pintype "bidirectional"))
    )
    (net (code "87") (name "TX0") (class "Default")
      (node (ref "1") (pin "1") (pinfunction "1_1") (pintype "passive"))
      (node (ref "ATMEGA2560") (pin "3") (pinfunction "(TXD0)PE1_3") (pintype "bidirectional"))
      (node (ref "IC5") (pin "5") (pinfunction "RXD_5") (pintype "input"))
    )
    (net (code "88") (name "TX1") (class "Default")
      (node (ref "18") (pin "1") (pinfunction "1_1") (pintype "passive"))
      (node (ref "ATMEGA2560") (pin "46") (pinfunction "(TXD1/INT3)PD3_46") (pintype "bidirectional"))
    )
    (net (code "89") (name "TX2") (class "Default")
      (node (ref "16") (pin "1") (pinfunction "1_1") (pintype "passive"))
      (node (ref "ATMEGA2560") (pin "13") (pinfunction "PH1(TXD2)_13") (pintype "bidirectional"))
    )
    (net (code "90") (name "TX3") (class "Default")
      (node (ref "14") (pin "1") (pinfunction "1_1") (pintype "passive"))
      (node (ref "ATMEGA2560") (pin "64") (pinfunction "PJ1(TXD3/PCINT10)_64") (pintype "bidirectional"))
    )
    (net (code "91") (name "unconnected-(ATMEGA2560-(CLKO{slash}ICP3{slash}INT7)PE7-Pad9)") (class "Default")
      (node (ref "ATMEGA2560") (pin "9") (pinfunction "(CLKO/ICP3/INT7)PE7_9") (pintype "bidirectional"))
    )
    (net (code "92") (name "unconnected-(ATMEGA2560-(ICP1)PD4-Pad47)") (class "Default")
      (node (ref "ATMEGA2560") (pin "47") (pinfunction "(ICP1)PD4_47") (pintype "bidirectional"))
    )
    (net (code "93") (name "unconnected-(ATMEGA2560-(T1)PD6-Pad49)") (class "Default")
      (node (ref "ATMEGA2560") (pin "49") (pinfunction "(T1)PD6_49") (pintype "bidirectional"))
    )
    (net (code "94") (name "unconnected-(ATMEGA2560-(T3{slash}INT6)PE6-Pad8)") (class "Default")
      (node (ref "ATMEGA2560") (pin "8") (pinfunction "(T3/INT6)PE6_8") (pintype "bidirectional"))
    )
    (net (code "95") (name "unconnected-(ATMEGA2560-(TOSC1)PG4-Pad29)") (class "Default")
      (node (ref "ATMEGA2560") (pin "29") (pinfunction "(TOSC1)PG4_29") (pintype "bidirectional"))
    )
    (net (code "96") (name "unconnected-(ATMEGA2560-(TOSC2)PG3-Pad28)") (class "Default")
      (node (ref "ATMEGA2560") (pin "28") (pinfunction "(TOSC2)PG3_28") (pintype "bidirectional"))
    )
    (net (code "97") (name "unconnected-(ATMEGA2560-(XCK0{slash}AIN0)PE2-Pad4)") (class "Default")
      (node (ref "ATMEGA2560") (pin "4") (pinfunction "(XCK0/AIN0)PE2_4") (pintype "bidirectional"))
    )
    (net (code "98") (name "unconnected-(ATMEGA2560-(XCK1)PD5-Pad48)") (class "Default")
      (node (ref "ATMEGA2560") (pin "48") (pinfunction "(XCK1)PD5_48") (pintype "bidirectional"))
    )
    (net (code "99") (name "unconnected-(ATMEGA2560-PH2(XCK2)-Pad14)") (class "Default")
      (node (ref "ATMEGA2560") (pin "14") (pinfunction "PH2(XCK2)_14") (pintype "bidirectional"))
    )
    (net (code "100") (name "unconnected-(ATMEGA2560-PH7(T4)-Pad27)") (class "Default")
      (node (ref "ATMEGA2560") (pin "27") (pinfunction "PH7(T4)_27") (pintype "bidirectional"))
    )
    (net (code "101") (name "unconnected-(ATMEGA2560-PJ2(XCK3{slash}PCINT11)-Pad65)") (class "Default")
      (node (ref "ATMEGA2560") (pin "65") (pinfunction "PJ2(XCK3/PCINT11)_65") (pintype "bidirectional"))
    )
    (net (code "102") (name "unconnected-(ATMEGA2560-PJ3(PCINT12)-Pad66)") (class "Default")
      (node (ref "ATMEGA2560") (pin "66") (pinfunction "PJ3(PCINT12)_66") (pintype "bidirectional"))
    )
    (net (code "103") (name "unconnected-(ATMEGA2560-PJ4(PCINT13)-Pad67)") (class "Default")
      (node (ref "ATMEGA2560") (pin "67") (pinfunction "PJ4(PCINT13)_67") (pintype "bidirectional"))
    )
    (net (code "104") (name "unconnected-(ATMEGA2560-PJ5(PCINT14)-Pad68)") (class "Default")
      (node (ref "ATMEGA2560") (pin "68") (pinfunction "PJ5(PCINT14)_68") (pintype "bidirectional"))
    )
    (net (code "105") (name "unconnected-(ATMEGA2560-PJ6(PCINT15)-Pad69)") (class "Default")
      (node (ref "ATMEGA2560") (pin "69") (pinfunction "PJ6(PCINT15)_69") (pintype "bidirectional"))
    )
    (net (code "106") (name "unconnected-(ATMEGA2560-PJ7-Pad79)") (class "Default")
      (node (ref "ATMEGA2560") (pin "79") (pinfunction "PJ7_79") (pintype "bidirectional"))
    )
    (net (code "107") (name "unconnected-(IC5-CBUS2-Pad13)") (class "Default")
      (node (ref "IC5") (pin "13") (pinfunction "CBUS2_13") (pintype "bidirectional"))
    )
    (net (code "108") (name "unconnected-(IC5-CBUS3-Pad14)") (class "Default")
      (node (ref "IC5") (pin "14") (pinfunction "CBUS3_14") (pintype "bidirectional"))
    )
    (net (code "109") (name "unconnected-(IC5-CBUS4-Pad12)") (class "Default")
      (node (ref "IC5") (pin "12") (pinfunction "CBUS4_12") (pintype "bidirectional"))
    )
    (net (code "110") (name "unconnected-(IC5-CTS#-Pad11)") (class "Default")
      (node (ref "IC5") (pin "11") (pinfunction "CTS#_11") (pintype "bidirectional"))
    )
    (net (code "111") (name "unconnected-(IC5-DCD#-Pad10)") (class "Default")
      (node (ref "IC5") (pin "10") (pinfunction "DCD#_10") (pintype "bidirectional"))
    )
    (net (code "112") (name "unconnected-(IC5-DSR#-Pad9)") (class "Default")
      (node (ref "IC5") (pin "9") (pinfunction "DSR#_9") (pintype "bidirectional"))
    )
    (net (code "113") (name "unconnected-(IC5-NC1-Pad8)") (class "Default")
      (node (ref "IC5") (pin "8") (pinfunction "NC1_8") (pintype "bidirectional"))
    )
    (net (code "114") (name "unconnected-(IC5-NC2-Pad24)") (class "Default")
      (node (ref "IC5") (pin "24") (pinfunction "NC2_24") (pintype "no_connect"))
    )
    (net (code "115") (name "unconnected-(IC5-OSCI-Pad27)") (class "Default")
      (node (ref "IC5") (pin "27") (pinfunction "OSCI_27") (pintype "bidirectional"))
    )
    (net (code "116") (name "unconnected-(IC5-OSCO-Pad28)") (class "Default")
      (node (ref "IC5") (pin "28") (pinfunction "OSCO_28") (pintype "output"))
    )
    (net (code "117") (name "unconnected-(IC5-RESET#-Pad19)") (class "Default")
      (node (ref "IC5") (pin "19") (pinfunction "RESET#_19") (pintype "bidirectional"))
    )
    (net (code "118") (name "unconnected-(IC5-RI#-Pad6)") (class "Default")
      (node (ref "IC5") (pin "6") (pinfunction "RI#_6") (pintype "bidirectional"))
    )
    (net (code "119") (name "unconnected-(IC5-RTS#-Pad3)") (class "Default")
      (node (ref "IC5") (pin "3") (pinfunction "RTS#_3") (pintype "output"))
    )
    (net (code "120") (name "unconnected-(J6-ID-Pad2)") (class "Default")
      (node (ref "J6") (pin "2") (pinfunction "ID_2") (pintype "bidirectional"))
    )
  )
)
